# mppt.net
KiCad netlist of a schematic drawn in EAGLE
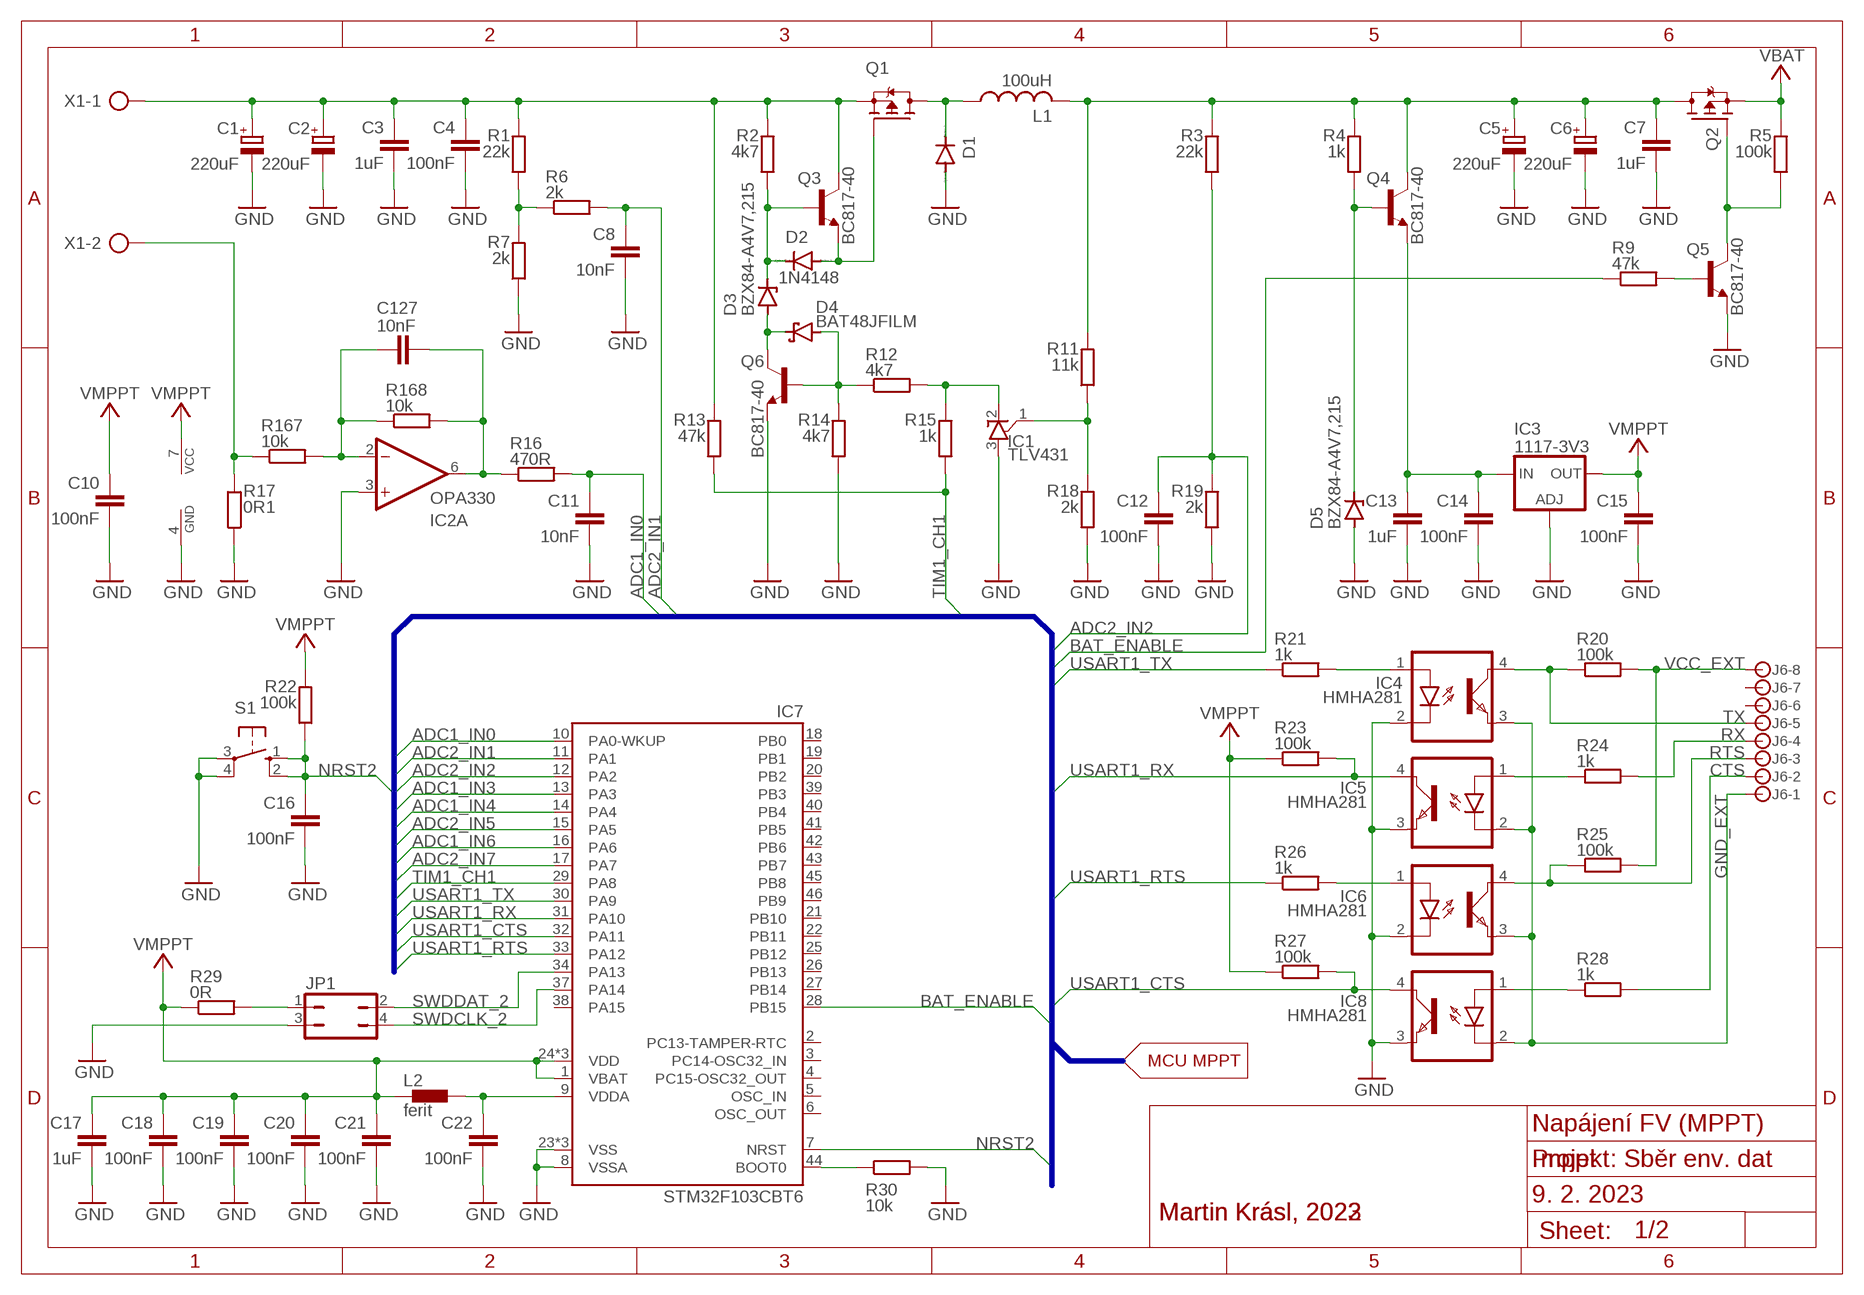
[diagram p0: schematic, sheet 1]
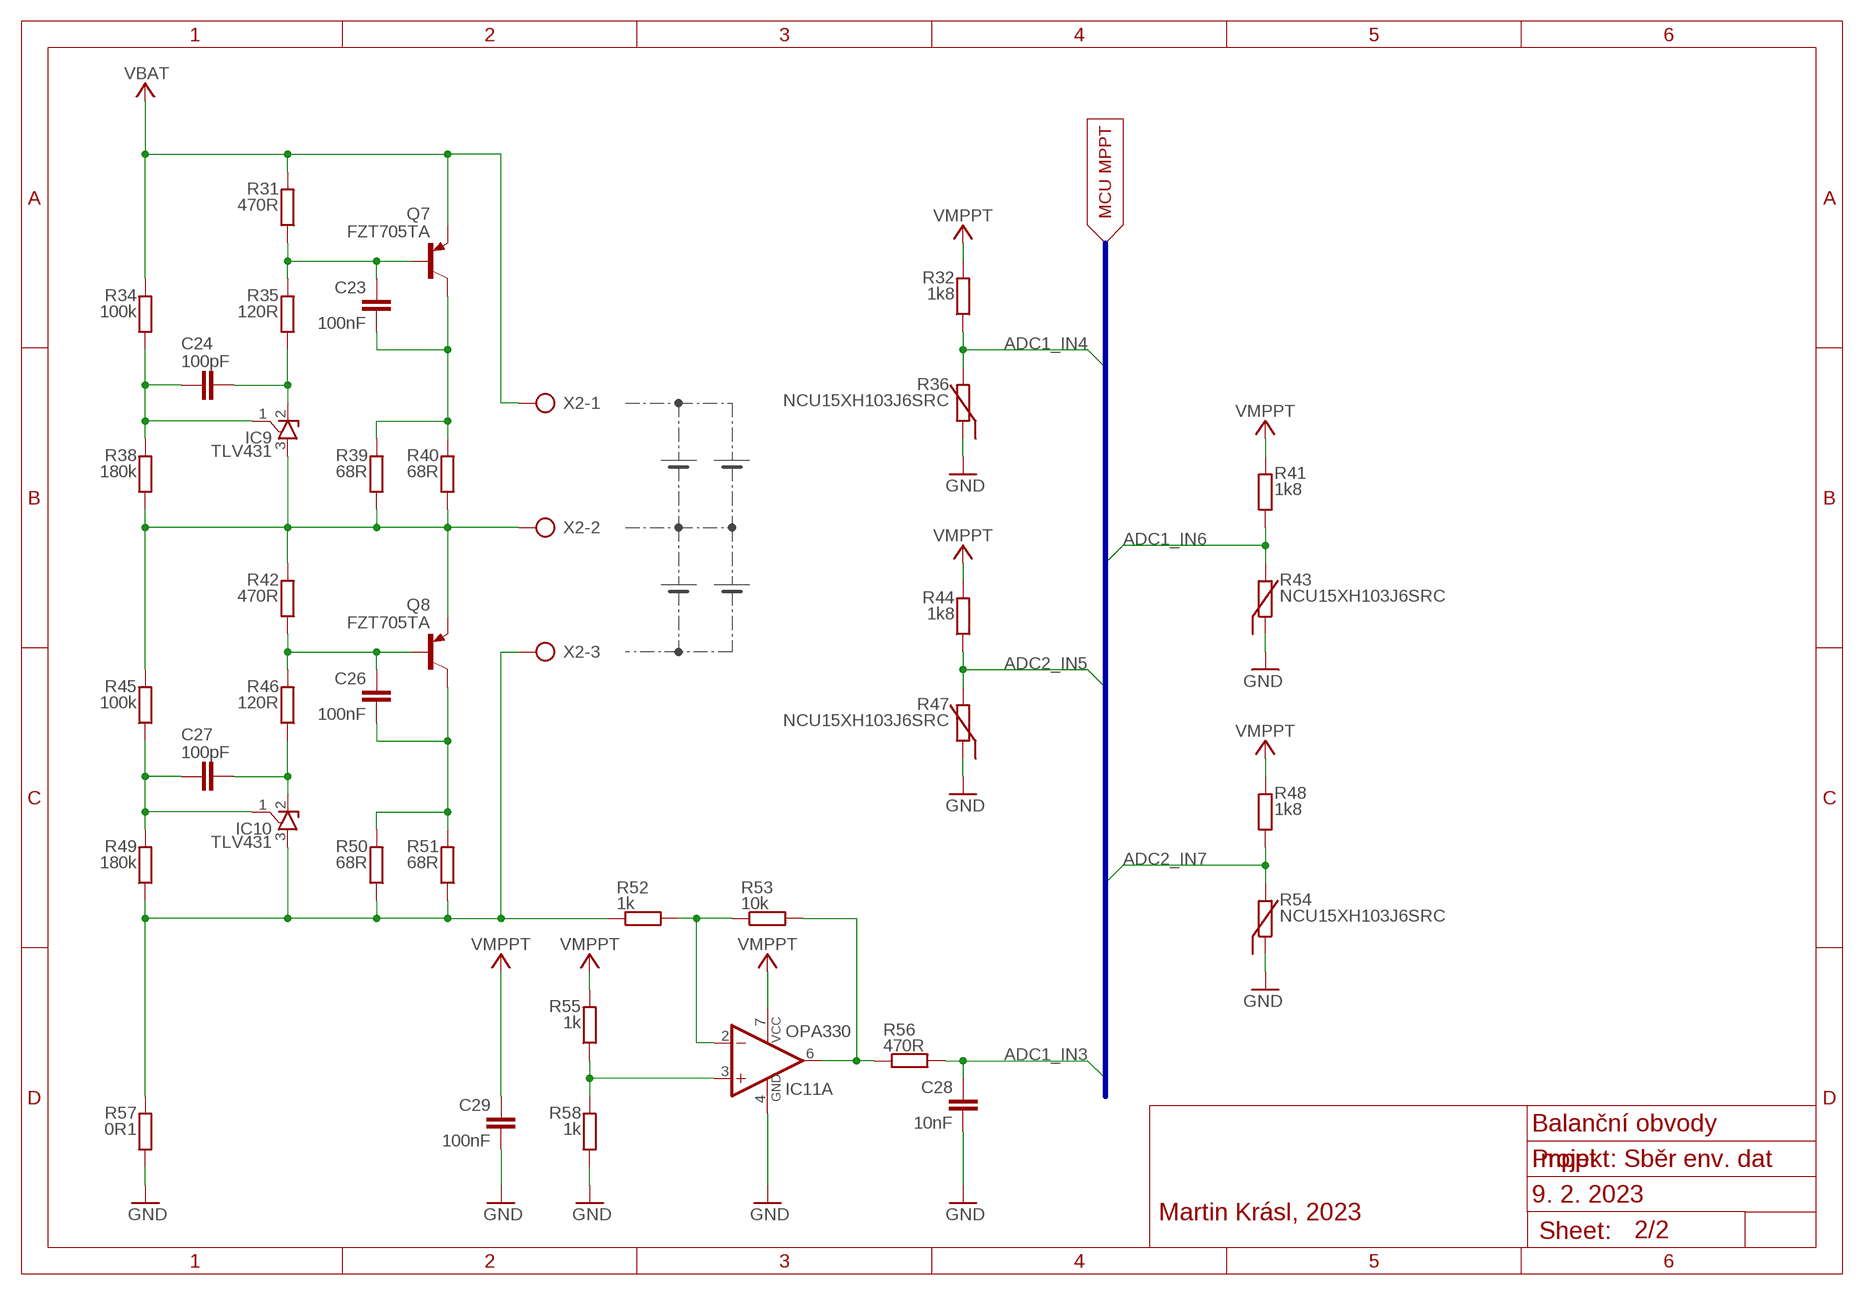
[diagram p1: schematic, sheet 2]

(export (version "E")
  (design (tool "Eeschema 10.0.6"))
  (components
    (comp (ref "C1")
      (value "220uF")
      (footprint "eagle-import:PANASONIC_G")
      (libsource (lib "eagle-import") (part "CPOL-EUG"))
    )
    (comp (ref "C2")
      (value "220uF")
      (footprint "eagle-import:PANASONIC_G")
      (libsource (lib "eagle-import") (part "CPOL-EUG"))
    )
    (comp (ref "C3")
      (value "1uF")
      (footprint "eagle-import:C0805")
      (libsource (lib "eagle-import") (part "C-EUC0805"))
    )
    (comp (ref "C4")
      (value "100nF")
      (footprint "eagle-import:C0402")
      (libsource (lib "eagle-import") (part "C-EUC0402"))
    )
    (comp (ref "C5")
      (value "220uF")
      (footprint "eagle-import:PANASONIC_G")
      (libsource (lib "eagle-import") (part "CPOL-EUG"))
    )
    (comp (ref "C6")
      (value "220uF")
      (footprint "eagle-import:PANASONIC_G")
      (libsource (lib "eagle-import") (part "CPOL-EUG"))
    )
    (comp (ref "C7")
      (value "1uF")
      (footprint "eagle-import:C0805")
      (libsource (lib "eagle-import") (part "C-EUC0805"))
    )
    (comp (ref "C8")
      (value "10nF")
      (footprint "eagle-import:C0402")
      (libsource (lib "eagle-import") (part "C-EUC0402"))
    )
    (comp (ref "C10")
      (value "100nF")
      (footprint "eagle-import:C0402")
      (libsource (lib "eagle-import") (part "C-EUC0402"))
    )
    (comp (ref "C11")
      (value "10nF")
      (footprint "eagle-import:C0402")
      (libsource (lib "eagle-import") (part "C-EUC0402"))
    )
    (comp (ref "C12")
      (value "100nF")
      (footprint "eagle-import:C0402")
      (libsource (lib "eagle-import") (part "C-EUC0402"))
    )
    (comp (ref "C13")
      (value "1uF")
      (footprint "eagle-import:C0805")
      (libsource (lib "eagle-import") (part "C-EUC0805"))
    )
    (comp (ref "C14")
      (value "100nF")
      (footprint "eagle-import:C0402")
      (libsource (lib "eagle-import") (part "C-EUC0402"))
    )
    (comp (ref "C15")
      (value "100nF")
      (footprint "eagle-import:C0402")
      (libsource (lib "eagle-import") (part "C-EUC0402"))
    )
    (comp (ref "C16")
      (value "100nF")
      (footprint "eagle-import:C0402")
      (libsource (lib "eagle-import") (part "C-EUC0402"))
    )
    (comp (ref "C17")
      (value "1uF")
      (footprint "eagle-import:C0805")
      (libsource (lib "eagle-import") (part "C-EUC0805"))
    )
    (comp (ref "C18")
      (value "100nF")
      (footprint "eagle-import:C0402")
      (libsource (lib "eagle-import") (part "C-EUC0402"))
    )
    (comp (ref "C19")
      (value "100nF")
      (footprint "eagle-import:C0402")
      (libsource (lib "eagle-import") (part "C-EUC0402"))
    )
    (comp (ref "C20")
      (value "100nF")
      (footprint "eagle-import:C0402")
      (libsource (lib "eagle-import") (part "C-EUC0402"))
    )
    (comp (ref "C21")
      (value "100nF")
      (footprint "eagle-import:C0402")
      (libsource (lib "eagle-import") (part "C-EUC0402"))
    )
    (comp (ref "C22")
      (value "100nF")
      (footprint "eagle-import:C0402")
      (libsource (lib "eagle-import") (part "C-EUC0402"))
    )
    (comp (ref "C127")
      (value "10nF")
      (footprint "eagle-import:C0402")
      (libsource (lib "eagle-import") (part "C-EUC0402"))
    )
    (comp (ref "D1")
      (value "#?")
      (footprint "eagle-import:SOD323")
      (libsource (lib "eagle-import") (part "1N4148"))
    )
    (comp (ref "D2")
      (value "1N4148")
      (footprint "eagle-import:SOD323")
      (libsource (lib "eagle-import") (part "1N4148"))
    )
    (comp (ref "D3")
      (value "BZX84-A4V7,215")
      (footprint "eagle-import:SOT23")
      (libsource (lib "eagle-import") (part "ZENER-DIODESOT23"))
    )
    (comp (ref "D4")
      (value "BAT48JFILM")
      (footprint "eagle-import:SOD323")
      (libsource (lib "eagle-import") (part "BAT48"))
    )
    (comp (ref "D5")
      (value "BZX84-A4V7,215")
      (footprint "eagle-import:SOT23")
      (libsource (lib "eagle-import") (part "ZENER-DIODESOT23"))
    )
    (comp (ref "IC1")
      (value "TLV431")
      (footprint "eagle-import:SOT23")
      (libsource (lib "eagle-import") (part "TLV431"))
    )
    (comp (ref "IC2")
      (value "OPA330")
      (footprint "eagle-import:SOIC-8")
      (libsource (lib "eagle-import") (part "OPA3"))
    )
    (comp (ref "IC3")
      (value "1117-3V3")
      (footprint "eagle-import:D2PACK")
      (libsource (lib "eagle-import") (part "LD117A?D2MTR"))
    )
    (comp (ref "IC4")
      (value "HMHA281")
      (footprint "eagle-import:SOIC127P680X239-4N")
      (fields (field (name "MOUSER_PART_NUMBER") "512-HMHA281"))
      (libsource (lib "eagle-import") (part "HMHA281"))
    )
    (comp (ref "IC5")
      (value "HMHA281")
      (footprint "eagle-import:SOIC127P680X239-4N")
      (fields (field (name "MOUSER_PART_NUMBER") "512-HMHA281"))
      (libsource (lib "eagle-import") (part "HMHA281"))
    )
    (comp (ref "IC6")
      (value "HMHA281")
      (footprint "eagle-import:SOIC127P680X239-4N")
      (fields (field (name "MOUSER_PART_NUMBER") "512-HMHA281"))
      (libsource (lib "eagle-import") (part "HMHA281"))
    )
    (comp (ref "IC7")
      (value "STM32F103CBT6")
      (footprint "eagle-import:QFP50P900X900X160-48N")
      (fields (field (name "MOUSER_PART_NUMBER") "511-STM32F103CBT6"))
      (libsource (lib "eagle-import") (part "STM32F103CBT6"))
    )
    (comp (ref "IC8")
      (value "HMHA281")
      (footprint "eagle-import:SOIC127P680X239-4N")
      (fields (field (name "MOUSER_PART_NUMBER") "512-HMHA281"))
      (libsource (lib "eagle-import") (part "HMHA281"))
    )
    (comp (ref "J6")
      (value "JST-XH-8")
      (footprint "eagle-import:B8B-XH-A")
      (fields (field (name "MF") "JST") (field (name "MPN") "B8B-XH-A"))
      (libsource (lib "eagle-import") (part "JST-XH-8"))
    )
    (comp (ref "JP1")
      (value "JP2Q")
      (footprint "eagle-import:JP2Q")
      (libsource (lib "eagle-import") (part "JP2Q"))
    )
    (comp (ref "L1")
      (value "100uH")
      (footprint "eagle-import:CEP125")
      (libsource (lib "eagle-import") (part "L-USCEP125"))
    )
    (comp (ref "L2")
      (value "ferit")
      (footprint "eagle-import:0402")
      (libsource (lib "eagle-import") (part "BLM15HB121SN1"))
    )
    (comp (ref "Q1")
      (value "#?")
      (footprint "eagle-import:SC74_INFINEON")
      (libsource (lib "eagle-import") (part "BSL207SP"))
    )
    (comp (ref "Q2")
      (value "#?")
      (footprint "eagle-import:SC74_INFINEON")
      (libsource (lib "eagle-import") (part "BSL207SP"))
    )
    (comp (ref "Q3")
      (value "BC817-40")
      (footprint "eagle-import:SOT23-BEC")
      (libsource (lib "eagle-import") (part "BC817SMD-16LT1"))
    )
    (comp (ref "Q4")
      (value "BC817-40")
      (footprint "eagle-import:SOT23-BEC")
      (libsource (lib "eagle-import") (part "BC817SMD-16LT1"))
    )
    (comp (ref "Q5")
      (value "BC817-40")
      (footprint "eagle-import:SOT23-BEC")
      (libsource (lib "eagle-import") (part "BC817SMD-16LT1"))
    )
    (comp (ref "Q6")
      (value "BC817-40")
      (footprint "eagle-import:SOT23-BEC")
      (libsource (lib "eagle-import") (part "BC817SMD-16LT1"))
    )
    (comp (ref "R1")
      (value "22k")
      (footprint "eagle-import:R0402")
      (libsource (lib "eagle-import") (part "R-EU_R0402"))
    )
    (comp (ref "R2")
      (value "4k7")
      (footprint "eagle-import:R0402")
      (libsource (lib "eagle-import") (part "R-EU_R0402"))
    )
    (comp (ref "R3")
      (value "22k")
      (footprint "eagle-import:R0402")
      (libsource (lib "eagle-import") (part "R-EU_R0402"))
    )
    (comp (ref "R4")
      (value "1k")
      (footprint "eagle-import:R0402")
      (libsource (lib "eagle-import") (part "R-EU_R0402"))
    )
    (comp (ref "R5")
      (value "100k")
      (footprint "eagle-import:R0402")
      (libsource (lib "eagle-import") (part "R-EU_R0402"))
    )
    (comp (ref "R6")
      (value "2k")
      (footprint "eagle-import:R0402")
      (libsource (lib "eagle-import") (part "R-EU_R0402"))
    )
    (comp (ref "R7")
      (value "2k")
      (footprint "eagle-import:R0402")
      (libsource (lib "eagle-import") (part "R-EU_R0402"))
    )
    (comp (ref "R9")
      (value "47k")
      (footprint "eagle-import:R0402")
      (libsource (lib "eagle-import") (part "R-EU_R0402"))
    )
    (comp (ref "R11")
      (value "11k")
      (footprint "eagle-import:R0402")
      (libsource (lib "eagle-import") (part "R-EU_R0402"))
    )
    (comp (ref "R12")
      (value "4k7")
      (footprint "eagle-import:R0402")
      (libsource (lib "eagle-import") (part "R-EU_R0402"))
    )
    (comp (ref "R13")
      (value "47k")
      (footprint "eagle-import:R0402")
      (libsource (lib "eagle-import") (part "R-EU_R0402"))
    )
    (comp (ref "R14")
      (value "4k7")
      (footprint "eagle-import:R0402")
      (libsource (lib "eagle-import") (part "R-EU_R0402"))
    )
    (comp (ref "R15")
      (value "1k")
      (footprint "eagle-import:R0402")
      (libsource (lib "eagle-import") (part "R-EU_R0402"))
    )
    (comp (ref "R16")
      (value "470R")
      (footprint "eagle-import:R0402")
      (libsource (lib "eagle-import") (part "R-EU_R0402"))
    )
    (comp (ref "R17")
      (value "0R1")
      (footprint "eagle-import:R0805")
      (libsource (lib "eagle-import") (part "R-EU_R0805"))
    )
    (comp (ref "R18")
      (value "2k")
      (footprint "eagle-import:R0402")
      (libsource (lib "eagle-import") (part "R-EU_R0402"))
    )
    (comp (ref "R19")
      (value "2k")
      (footprint "eagle-import:R0402")
      (libsource (lib "eagle-import") (part "R-EU_R0402"))
    )
    (comp (ref "R20")
      (value "100k")
      (footprint "eagle-import:R0402")
      (libsource (lib "eagle-import") (part "R-EU_R0402"))
    )
    (comp (ref "R21")
      (value "1k")
      (footprint "eagle-import:R0402")
      (libsource (lib "eagle-import") (part "R-EU_R0402"))
    )
    (comp (ref "R22")
      (value "100k")
      (footprint "eagle-import:R0402")
      (libsource (lib "eagle-import") (part "R-EU_R0402"))
    )
    (comp (ref "R23")
      (value "100k")
      (footprint "eagle-import:R0402")
      (libsource (lib "eagle-import") (part "R-EU_R0402"))
    )
    (comp (ref "R24")
      (value "1k")
      (footprint "eagle-import:R0402")
      (libsource (lib "eagle-import") (part "R-EU_R0402"))
    )
    (comp (ref "R25")
      (value "100k")
      (footprint "eagle-import:R0402")
      (libsource (lib "eagle-import") (part "R-EU_R0402"))
    )
    (comp (ref "R26")
      (value "1k")
      (footprint "eagle-import:R0402")
      (libsource (lib "eagle-import") (part "R-EU_R0402"))
    )
    (comp (ref "R27")
      (value "100k")
      (footprint "eagle-import:R0402")
      (libsource (lib "eagle-import") (part "R-EU_R0402"))
    )
    (comp (ref "R28")
      (value "1k")
      (footprint "eagle-import:R0402")
      (libsource (lib "eagle-import") (part "R-EU_R0402"))
    )
    (comp (ref "R29")
      (value "0R")
      (footprint "eagle-import:R0402")
      (libsource (lib "eagle-import") (part "R-EU_R0402"))
    )
    (comp (ref "R30")
      (value "10k")
      (footprint "eagle-import:R0402")
      (libsource (lib "eagle-import") (part "R-EU_R0402"))
    )
    (comp (ref "R167")
      (value "10k")
      (footprint "eagle-import:R0402")
      (libsource (lib "eagle-import") (part "R-EU_R0402"))
    )
    (comp (ref "R168")
      (value "10k")
      (footprint "eagle-import:R0402")
      (libsource (lib "eagle-import") (part "R-EU_R0402"))
    )
    (comp (ref "S1")
      (value "10-XX")
      (footprint "eagle-import:B3F-10XX")
      (fields (field (name "MPN") "B3F-1000"))
      (libsource (lib "eagle-import") (part "10-XX"))
    )
    (comp (ref "X1")
      (value "AK500/2")
      (footprint "eagle-import:AK500_2")
      (libsource (lib "eagle-import") (part "AK500/2"))
    )
    (comp (ref "C23")
      (value "100nF")
      (footprint "eagle-import:C0402")
      (libsource (lib "eagle-import") (part "C-EUC0402"))
    )
    (comp (ref "C24")
      (value "100pF")
      (footprint "eagle-import:C0402")
      (libsource (lib "eagle-import") (part "C-EUC0402"))
    )
    (comp (ref "C26")
      (value "100nF")
      (footprint "eagle-import:C0402")
      (libsource (lib "eagle-import") (part "C-EUC0402"))
    )
    (comp (ref "C27")
      (value "100pF")
      (footprint "eagle-import:C0402")
      (libsource (lib "eagle-import") (part "C-EUC0402"))
    )
    (comp (ref "C28")
      (value "10nF")
      (footprint "eagle-import:C0402")
      (libsource (lib "eagle-import") (part "C-EUC0402"))
    )
    (comp (ref "C29")
      (value "100nF")
      (footprint "eagle-import:C0402")
      (libsource (lib "eagle-import") (part "C-EUC0402"))
    )
    (comp (ref "IC9")
      (value "TLV431")
      (footprint "eagle-import:SOT23")
      (libsource (lib "eagle-import") (part "TLV431"))
    )
    (comp (ref "IC10")
      (value "TLV431")
      (footprint "eagle-import:SOT23")
      (libsource (lib "eagle-import") (part "TLV431"))
    )
    (comp (ref "IC11")
      (value "OPA330")
      (footprint "eagle-import:SOIC-8")
      (libsource (lib "eagle-import") (part "OPA3"))
    )
    (comp (ref "Q7")
      (value "FZT705TA")
      (footprint "eagle-import:SOT223")
      (libsource (lib "eagle-import") (part "FZT753SMD"))
    )
    (comp (ref "Q8")
      (value "FZT705TA")
      (footprint "eagle-import:SOT223")
      (libsource (lib "eagle-import") (part "FZT753SMD"))
    )
    (comp (ref "R31")
      (value "470R")
      (footprint "eagle-import:R0402")
      (libsource (lib "eagle-import") (part "R-EU_R0402"))
    )
    (comp (ref "R32")
      (value "1k8")
      (footprint "eagle-import:R0402")
      (libsource (lib "eagle-import") (part "R-EU_R0402"))
    )
    (comp (ref "R34")
      (value "100k")
      (footprint "eagle-import:R0402")
      (libsource (lib "eagle-import") (part "R-EU_R0402"))
    )
    (comp (ref "R35")
      (value "120R")
      (footprint "eagle-import:R0402")
      (libsource (lib "eagle-import") (part "R-EU_R0402"))
    )
    (comp (ref "R36")
      (value "NCU15XH103J6SRC")
      (footprint "eagle-import:R0402")
      (libsource (lib "eagle-import") (part "NCU15XH103J6SRC"))
    )
    (comp (ref "R38")
      (value "180k")
      (footprint "eagle-import:R0402")
      (libsource (lib "eagle-import") (part "R-EU_R0402"))
    )
    (comp (ref "R39")
      (value "68R")
      (footprint "eagle-import:R2512")
      (libsource (lib "eagle-import") (part "R-EU_R2512"))
    )
    (comp (ref "R40")
      (value "68R")
      (footprint "eagle-import:R2512")
      (libsource (lib "eagle-import") (part "R-EU_R2512"))
    )
    (comp (ref "R41")
      (value "1k8")
      (footprint "eagle-import:R0402")
      (libsource (lib "eagle-import") (part "R-EU_R0402"))
    )
    (comp (ref "R42")
      (value "470R")
      (footprint "eagle-import:R0402")
      (libsource (lib "eagle-import") (part "R-EU_R0402"))
    )
    (comp (ref "R43")
      (value "NCU15XH103J6SRC")
      (footprint "eagle-import:R0402")
      (libsource (lib "eagle-import") (part "NCU15XH103J6SRC"))
    )
    (comp (ref "R44")
      (value "1k8")
      (footprint "eagle-import:R0402")
      (libsource (lib "eagle-import") (part "R-EU_R0402"))
    )
    (comp (ref "R45")
      (value "100k")
      (footprint "eagle-import:R0402")
      (libsource (lib "eagle-import") (part "R-EU_R0402"))
    )
    (comp (ref "R46")
      (value "120R")
      (footprint "eagle-import:R0402")
      (libsource (lib "eagle-import") (part "R-EU_R0402"))
    )
    (comp (ref "R47")
      (value "NCU15XH103J6SRC")
      (footprint "eagle-import:R0402")
      (libsource (lib "eagle-import") (part "NCU15XH103J6SRC"))
    )
    (comp (ref "R48")
      (value "1k8")
      (footprint "eagle-import:R0402")
      (libsource (lib "eagle-import") (part "R-EU_R0402"))
    )
    (comp (ref "R49")
      (value "180k")
      (footprint "eagle-import:R0402")
      (libsource (lib "eagle-import") (part "R-EU_R0402"))
    )
    (comp (ref "R50")
      (value "68R")
      (footprint "eagle-import:R2512")
      (libsource (lib "eagle-import") (part "R-EU_R2512"))
    )
    (comp (ref "R51")
      (value "68R")
      (footprint "eagle-import:R2512")
      (libsource (lib "eagle-import") (part "R-EU_R2512"))
    )
    (comp (ref "R52")
      (value "1k")
      (footprint "eagle-import:R0402")
      (libsource (lib "eagle-import") (part "R-EU_R0402"))
    )
    (comp (ref "R53")
      (value "10k")
      (footprint "eagle-import:R0402")
      (libsource (lib "eagle-import") (part "R-EU_R0402"))
    )
    (comp (ref "R54")
      (value "NCU15XH103J6SRC")
      (footprint "eagle-import:R0402")
      (libsource (lib "eagle-import") (part "NCU15XH103J6SRC"))
    )
    (comp (ref "R55")
      (value "1k")
      (footprint "eagle-import:R0402")
      (libsource (lib "eagle-import") (part "R-EU_R0402"))
    )
    (comp (ref "R56")
      (value "470R")
      (footprint "eagle-import:R0402")
      (libsource (lib "eagle-import") (part "R-EU_R0402"))
    )
    (comp (ref "R57")
      (value "0R1")
      (footprint "eagle-import:R0805")
      (libsource (lib "eagle-import") (part "R-EU_R0805"))
    )
    (comp (ref "R58")
      (value "1k")
      (footprint "eagle-import:R0402")
      (libsource (lib "eagle-import") (part "R-EU_R0402"))
    )
    (comp (ref "X2")
      (value "AK500/3")
      (footprint "eagle-import:AK500_3")
      (libsource (lib "eagle-import") (part "AK500/3"))
    )
  )
  (nets
    (net (code "1") (name "ADC1_IN0") (class "Default")
      (node (ref "C11") (pin "1") (pinfunction "1_1") (pintype "passive"))
      (node (ref "IC7") (pin "10") (pinfunction "PA0-WKUP_10") (pintype "bidirectional"))
      (node (ref "R16") (pin "2") (pinfunction "2_2") (pintype "passive"))
    )
    (net (code "2") (name "ADC1_IN3") (class "Default")
      (node (ref "C28") (pin "1") (pinfunction "1_1") (pintype "passive"))
      (node (ref "IC7") (pin "13") (pinfunction "PA3_13") (pintype "bidirectional"))
      (node (ref "R56") (pin "2") (pinfunction "2_2") (pintype "passive"))
    )
    (net (code "3") (name "ADC1_IN4") (class "Default")
      (node (ref "IC7") (pin "14") (pinfunction "PA4_14") (pintype "bidirectional"))
      (node (ref "R32") (pin "1") (pinfunction "1_1") (pintype "passive"))
      (node (ref "R36") (pin "2") (pinfunction "2_2") (pintype "passive"))
    )
    (net (code "4") (name "ADC1_IN6") (class "Default")
      (node (ref "IC7") (pin "16") (pinfunction "PA6_16") (pintype "bidirectional"))
      (node (ref "R41") (pin "1") (pinfunction "1_1") (pintype "passive"))
      (node (ref "R43") (pin "2") (pinfunction "2_2") (pintype "passive"))
    )
    (net (code "5") (name "ADC2_IN1") (class "Default")
      (node (ref "C8") (pin "1") (pinfunction "1_1") (pintype "passive"))
      (node (ref "IC7") (pin "11") (pinfunction "PA1_11") (pintype "bidirectional"))
      (node (ref "R6") (pin "2") (pinfunction "2_2") (pintype "passive"))
    )
    (net (code "6") (name "ADC2_IN2") (class "Default")
      (node (ref "C12") (pin "1") (pinfunction "1_1") (pintype "passive"))
      (node (ref "IC7") (pin "12") (pinfunction "PA2_12") (pintype "bidirectional"))
      (node (ref "R19") (pin "2") (pinfunction "2_2") (pintype "passive"))
      (node (ref "R3") (pin "1") (pinfunction "1_1") (pintype "passive"))
    )
    (net (code "7") (name "ADC2_IN5") (class "Default")
      (node (ref "IC7") (pin "15") (pinfunction "PA5_15") (pintype "bidirectional"))
      (node (ref "R44") (pin "1") (pinfunction "1_1") (pintype "passive"))
      (node (ref "R47") (pin "2") (pinfunction "2_2") (pintype "passive"))
    )
    (net (code "8") (name "ADC2_IN7") (class "Default")
      (node (ref "IC7") (pin "17") (pinfunction "PA7_17") (pintype "bidirectional"))
      (node (ref "R48") (pin "1") (pinfunction "1_1") (pintype "passive"))
      (node (ref "R54") (pin "2") (pinfunction "2_2") (pintype "passive"))
    )
    (net (code "9") (name "BAT_ENABLE") (class "Default")
      (node (ref "IC7") (pin "28") (pinfunction "PB15_28") (pintype "bidirectional"))
      (node (ref "R9") (pin "1") (pinfunction "1_1") (pintype "passive"))
    )
    (net (code "10") (name "CTS") (class "Default")
      (node (ref "J6") (pin "2") (pinfunction "P_2") (pintype "bidirectional"))
      (node (ref "R28") (pin "2") (pinfunction "2_2") (pintype "passive"))
    )
    (net (code "11") (name "GND") (class "Default")
      (node (ref "C1") (pin "-") (pinfunction "-_-") (pintype "passive"))
      (node (ref "C10") (pin "2") (pinfunction "2_2") (pintype "passive"))
      (node (ref "C11") (pin "2") (pinfunction "2_2") (pintype "passive"))
      (node (ref "C12") (pin "2") (pinfunction "2_2") (pintype "passive"))
      (node (ref "C13") (pin "2") (pinfunction "2_2") (pintype "passive"))
      (node (ref "C14") (pin "2") (pinfunction "2_2") (pintype "passive"))
      (node (ref "C15") (pin "2") (pinfunction "2_2") (pintype "passive"))
      (node (ref "C16") (pin "2") (pinfunction "2_2") (pintype "passive"))
      (node (ref "C17") (pin "2") (pinfunction "2_2") (pintype "passive"))
      (node (ref "C18") (pin "2") (pinfunction "2_2") (pintype "passive"))
      (node (ref "C19") (pin "2") (pinfunction "2_2") (pintype "passive"))
      (node (ref "C2") (pin "-") (pinfunction "-_-") (pintype "passive"))
      (node (ref "C20") (pin "2") (pinfunction "2_2") (pintype "passive"))
      (node (ref "C21") (pin "2") (pinfunction "2_2") (pintype "passive"))
      (node (ref "C22") (pin "2") (pinfunction "2_2") (pintype "passive"))
      (node (ref "C28") (pin "2") (pinfunction "2_2") (pintype "passive"))
      (node (ref "C29") (pin "2") (pinfunction "2_2") (pintype "passive"))
      (node (ref "C3") (pin "2") (pinfunction "2_2") (pintype "passive"))
      (node (ref "C4") (pin "2") (pinfunction "2_2") (pintype "passive"))
      (node (ref "C5") (pin "-") (pinfunction "-_-") (pintype "passive"))
      (node (ref "C6") (pin "-") (pinfunction "-_-") (pintype "passive"))
      (node (ref "C7") (pin "2") (pinfunction "2_2") (pintype "passive"))
      (node (ref "C8") (pin "2") (pinfunction "2_2") (pintype "passive"))
      (node (ref "D1") (pin "2") (pinfunction "A_2") (pintype "passive"))
      (node (ref "D5") (pin "1") (pinfunction "A_1") (pintype "passive"))
      (node (ref "IC1") (pin "3") (pinfunction "A_3") (pintype "passive"))
      (node (ref "IC11") (pin "4") (pinfunction "GND_4") (pintype "power_in"))
      (node (ref "IC2") (pin "3") (pinfunction "+IN_3") (pintype "input"))
      (node (ref "IC2") (pin "4") (pinfunction "GND_4") (pintype "power_in"))
      (node (ref "IC3") (pin "1") (pinfunction "ADJ_1") (pintype "input"))
      (node (ref "IC4") (pin "2") (pinfunction "K_2") (pintype "bidirectional"))
      (node (ref "IC5") (pin "3") (pinfunction "E_3") (pintype "bidirectional"))
      (node (ref "IC6") (pin "2") (pinfunction "K_2") (pintype "bidirectional"))
      (node (ref "IC7") (pin "23") (pinfunction "VSS_23") (pintype "bidirectional"))
      (node (ref "IC7") (pin "35") (pinfunction "VSS_35") (pintype "bidirectional"))
      (node (ref "IC7") (pin "47") (pinfunction "VSS_47") (pintype "bidirectional"))
      (node (ref "IC7") (pin "8") (pinfunction "VSSA_8") (pintype "bidirectional"))
      (node (ref "IC8") (pin "3") (pinfunction "E_3") (pintype "bidirectional"))
      (node (ref "JP1") (pin "3") (pinfunction "3_3") (pintype "passive"))
      (node (ref "Q5") (pin "E") (pinfunction "E_E") (pintype "passive"))
      (node (ref "Q6") (pin "E") (pinfunction "E_E") (pintype "passive"))
      (node (ref "R14") (pin "1") (pinfunction "1_1") (pintype "passive"))
      (node (ref "R17") (pin "1") (pinfunction "1_1") (pintype "passive"))
      (node (ref "R18") (pin "1") (pinfunction "1_1") (pintype "passive"))
      (node (ref "R19") (pin "1") (pinfunction "1_1") (pintype "passive"))
      (node (ref "R30") (pin "2") (pinfunction "2_2") (pintype "passive"))
      (node (ref "R36") (pin "1") (pinfunction "1_1") (pintype "passive"))
      (node (ref "R43") (pin "1") (pinfunction "1_1") (pintype "passive"))
      (node (ref "R47") (pin "1") (pinfunction "1_1") (pintype "passive"))
      (node (ref "R54") (pin "1") (pinfunction "1_1") (pintype "passive"))
      (node (ref "R57") (pin "1") (pinfunction "1_1") (pintype "passive"))
      (node (ref "R58") (pin "1") (pinfunction "1_1") (pintype "passive"))
      (node (ref "R7") (pin "1") (pinfunction "1_1") (pintype "passive"))
      (node (ref "S1") (pin "3") (pinfunction "P_3") (pintype "passive"))
      (node (ref "S1") (pin "4") (pinfunction "P1_4") (pintype "passive"))
    )
    (net (code "12") (name "GND_EXT") (class "Default")
      (node (ref "IC4") (pin "3") (pinfunction "E_3") (pintype "bidirectional"))
      (node (ref "IC5") (pin "2") (pinfunction "K_2") (pintype "bidirectional"))
      (node (ref "IC6") (pin "3") (pinfunction "E_3") (pintype "bidirectional"))
      (node (ref "IC8") (pin "2") (pinfunction "K_2") (pintype "bidirectional"))
      (node (ref "J6") (pin "1") (pinfunction "P_1") (pintype "bidirectional"))
    )
    (net (code "13") (name "NRST2") (class "Default")
      (node (ref "C16") (pin "1") (pinfunction "1_1") (pintype "passive"))
      (node (ref "IC7") (pin "7") (pinfunction "NRST_7") (pintype "bidirectional"))
      (node (ref "R22") (pin "1") (pinfunction "1_1") (pintype "passive"))
      (node (ref "S1") (pin "1") (pinfunction "S_1") (pintype "passive"))
      (node (ref "S1") (pin "2") (pinfunction "S1_2") (pintype "passive"))
    )
    (net (code "14") (name "Net-(C5-Pad+)") (class "Default")
      (node (ref "C5") (pin "+") (pinfunction "+_+") (pintype "passive"))
      (node (ref "C6") (pin "+") (pinfunction "+_+") (pintype "passive"))
      (node (ref "C7") (pin "1") (pinfunction "1_1") (pintype "passive"))
      (node (ref "L1") (pin "2") (pinfunction "2_2") (pintype "passive"))
      (node (ref "Q2") (pin "1") (pinfunction "D_1") (pintype "passive"))
      (node (ref "Q2") (pin "2") (pinfunction "D_2") (pintype "passive"))
      (node (ref "Q2") (pin "5") (pinfunction "D_5") (pintype "passive"))
      (node (ref "Q2") (pin "6") (pinfunction "D_6") (pintype "passive"))
      (node (ref "Q4") (pin "C") (pinfunction "C_C") (pintype "passive"))
      (node (ref "R11") (pin "2") (pinfunction "2_2") (pintype "passive"))
      (node (ref "R3") (pin "2") (pinfunction "2_2") (pintype "passive"))
      (node (ref "R4") (pin "2") (pinfunction "2_2") (pintype "passive"))
    )
    (net (code "15") (name "Net-(C23-Pad2)") (class "Default")
      (node (ref "C23") (pin "2") (pinfunction "2_2") (pintype "passive"))
      (node (ref "Q7") (pin "2") (pinfunction "C_2") (pintype "passive"))
      (node (ref "Q7") (pin "4") (pinfunction "C_4") (pintype "passive"))
      (node (ref "R39") (pin "2") (pinfunction "2_2") (pintype "passive"))
      (node (ref "R40") (pin "2") (pinfunction "2_2") (pintype "passive"))
    )
    (net (code "16") (name "Net-(C26-Pad2)") (class "Default")
      (node (ref "C26") (pin "2") (pinfunction "2_2") (pintype "passive"))
      (node (ref "Q8") (pin "2") (pinfunction "C_2") (pintype "passive"))
      (node (ref "Q8") (pin "4") (pinfunction "C_4") (pintype "passive"))
      (node (ref "R50") (pin "2") (pinfunction "2_2") (pintype "passive"))
      (node (ref "R51") (pin "2") (pinfunction "2_2") (pintype "passive"))
    )
    (net (code "17") (name "Net-(D1-C)") (class "Default")
      (node (ref "D1") (pin "1") (pinfunction "C_1") (pintype "passive"))
      (node (ref "L1") (pin "1") (pinfunction "1_1") (pintype "passive"))
      (node (ref "Q1") (pin "1") (pinfunction "D_1") (pintype "passive"))
      (node (ref "Q1") (pin "2") (pinfunction "D_2") (pintype "passive"))
      (node (ref "Q1") (pin "5") (pinfunction "D_5") (pintype "passive"))
      (node (ref "Q1") (pin "6") (pinfunction "D_6") (pintype "passive"))
    )
    (net (code "18") (name "Net-(D2-A)") (class "Default")
      (node (ref "D2") (pin "2") (pinfunction "A_2") (pintype "passive"))
      (node (ref "Q1") (pin "3") (pinfunction "G_3") (pintype "passive"))
      (node (ref "Q3") (pin "E") (pinfunction "E_E") (pintype "passive"))
    )
    (net (code "19") (name "Net-(D2-C)") (class "Default")
      (node (ref "D2") (pin "1") (pinfunction "C_1") (pintype "passive"))
      (node (ref "D3") (pin "3") (pinfunction "C_3") (pintype "passive"))
      (node (ref "Q3") (pin "B") (pinfunction "B_B") (pintype "passive"))
      (node (ref "R2") (pin "1") (pinfunction "1_1") (pintype "passive"))
    )
    (net (code "20") (name "Net-(D3-A)") (class "Default")
      (node (ref "D3") (pin "1") (pinfunction "A_1") (pintype "passive"))
      (node (ref "D4") (pin "1") (pinfunction "C_1") (pintype "passive"))
      (node (ref "Q6") (pin "C") (pinfunction "C_C") (pintype "passive"))
    )
    (net (code "21") (name "Net-(D4-A)") (class "Default")
      (node (ref "D4") (pin "2") (pinfunction "A_2") (pintype "passive"))
      (node (ref "Q6") (pin "B") (pinfunction "B_B") (pintype "passive"))
      (node (ref "R12") (pin "1") (pinfunction "1_1") (pintype "passive"))
      (node (ref "R14") (pin "2") (pinfunction "2_2") (pintype "passive"))
    )
    (net (code "22") (name "Net-(D5-C)") (class "Default")
      (node (ref "D5") (pin "3") (pinfunction "C_3") (pintype "passive"))
      (node (ref "Q4") (pin "B") (pinfunction "B_B") (pintype "passive"))
      (node (ref "R4") (pin "1") (pinfunction "1_1") (pintype "passive"))
    )
    (net (code "23") (name "Net-(IC1-C)") (class "Default")
      (node (ref "IC1") (pin "2") (pinfunction "C_2") (pintype "passive"))
      (node (ref "R12") (pin "2") (pinfunction "2_2") (pintype "passive"))
      (node (ref "R15") (pin "2") (pinfunction "2_2") (pintype "passive"))
    )
    (net (code "24") (name "Net-(IC1-R)") (class "Default")
      (node (ref "IC1") (pin "1") (pinfunction "R_1") (pintype "passive"))
      (node (ref "R11") (pin "1") (pinfunction "1_1") (pintype "passive"))
      (node (ref "R18") (pin "2") (pinfunction "2_2") (pintype "passive"))
    )
    (net (code "25") (name "Net-(IC2A--IN)") (class "Default")
      (node (ref "C127") (pin "1") (pinfunction "1_1") (pintype "passive"))
      (node (ref "IC2") (pin "2") (pinfunction "-IN_2") (pintype "input"))
      (node (ref "R167") (pin "2") (pinfunction "2_2") (pintype "passive"))
      (node (ref "R168") (pin "1") (pinfunction "1_1") (pintype "passive"))
    )
    (net (code "26") (name "Net-(IC2A-OUT)") (class "Default")
      (node (ref "C127") (pin "2") (pinfunction "2_2") (pintype "passive"))
      (node (ref "IC2") (pin "6") (pinfunction "OUT_6") (pintype "output"))
      (node (ref "R16") (pin "1") (pinfunction "1_1") (pintype "passive"))
      (node (ref "R168") (pin "2") (pinfunction "2_2") (pintype "passive"))
    )
    (net (code "27") (name "Net-(IC3-IN)") (class "Default")
      (node (ref "C13") (pin "1") (pinfunction "1_1") (pintype "passive"))
      (node (ref "C14") (pin "1") (pinfunction "1_1") (pintype "passive"))
      (node (ref "IC3") (pin "3") (pinfunction "IN_3") (pintype "input"))
      (node (ref "Q4") (pin "E") (pinfunction "E_E") (pintype "passive"))
    )
    (net (code "28") (name "Net-(IC4-A)") (class "Default")
      (node (ref "IC4") (pin "1") (pinfunction "A_1") (pintype "bidirectional"))
      (node (ref "R21") (pin "2") (pinfunction "2_2") (pintype "passive"))
    )
    (net (code "29") (name "Net-(IC5-A)") (class "Default")
      (node (ref "IC5") (pin "1") (pinfunction "A_1") (pintype "bidirectional"))
      (node (ref "R24") (pin "1") (pinfunction "1_1") (pintype "passive"))
    )
    (net (code "30") (name "Net-(IC6-A)") (class "Default")
      (node (ref "IC6") (pin "1") (pinfunction "A_1") (pintype "bidirectional"))
      (node (ref "R26") (pin "2") (pinfunction "2_2") (pintype "passive"))
    )
    (net (code "31") (name "Net-(IC7-BOOT0)") (class "Default")
      (node (ref "IC7") (pin "44") (pinfunction "BOOT0_44") (pintype "bidirectional"))
      (node (ref "R30") (pin "1") (pinfunction "1_1") (pintype "passive"))
    )
    (net (code "32") (name "Net-(IC7-VDDA)") (class "Default")
      (node (ref "C22") (pin "1") (pinfunction "1_1") (pintype "passive"))
      (node (ref "IC7") (pin "9") (pinfunction "VDDA_9") (pintype "bidirectional"))
      (node (ref "L2") (pin "2") (pinfunction "2_2") (pintype "passive"))
    )
    (net (code "33") (name "Net-(IC8-A)") (class "Default")
      (node (ref "IC8") (pin "1") (pinfunction "A_1") (pintype "bidirectional"))
      (node (ref "R28") (pin "1") (pinfunction "1_1") (pintype "passive"))
    )
    (net (code "34") (name "Net-(IC9-A)") (class "Default")
      (node (ref "IC9") (pin "3") (pinfunction "A_3") (pintype "passive"))
      (node (ref "Q8") (pin "3") (pinfunction "E_3") (pintype "passive"))
      (node (ref "R38") (pin "1") (pinfunction "1_1") (pintype "passive"))
      (node (ref "R39") (pin "1") (pinfunction "1_1") (pintype "passive"))
      (node (ref "R40") (pin "1") (pinfunction "1_1") (pintype "passive"))
      (node (ref "R42") (pin "2") (pinfunction "2_2") (pintype "passive"))
      (node (ref "R45") (pin "2") (pinfunction "2_2") (pintype "passive"))
      (node (ref "X2") (pin "2") (pinfunction "KL_2") (pintype "passive"))
    )
    (net (code "35") (name "Net-(IC9-C)") (class "Default")
      (node (ref "C24") (pin "2") (pinfunction "2_2") (pintype "passive"))
      (node (ref "IC9") (pin "2") (pinfunction "C_2") (pintype "passive"))
      (node (ref "R35") (pin "1") (pinfunction "1_1") (pintype "passive"))
    )
    (net (code "36") (name "Net-(IC9-R)") (class "Default")
      (node (ref "C24") (pin "1") (pinfunction "1_1") (pintype "passive"))
      (node (ref "IC9") (pin "1") (pinfunction "R_1") (pintype "passive"))
      (node (ref "R34") (pin "1") (pinfunction "1_1") (pintype "passive"))
      (node (ref "R38") (pin "2") (pinfunction "2_2") (pintype "passive"))
    )
    (net (code "37") (name "Net-(IC10-A)") (class "Default")
      (node (ref "IC10") (pin "3") (pinfunction "A_3") (pintype "passive"))
      (node (ref "R49") (pin "1") (pinfunction "1_1") (pintype "passive"))
      (node (ref "R50") (pin "1") (pinfunction "1_1") (pintype "passive"))
      (node (ref "R51") (pin "1") (pinfunction "1_1") (pintype "passive"))
      (node (ref "R52") (pin "1") (pinfunction "1_1") (pintype "passive"))
      (node (ref "R57") (pin "2") (pinfunction "2_2") (pintype "passive"))
      (node (ref "X2") (pin "3") (pinfunction "KL_3") (pintype "passive"))
    )
    (net (code "38") (name "Net-(IC10-C)") (class "Default")
      (node (ref "C27") (pin "2") (pinfunction "2_2") (pintype "passive"))
      (node (ref "IC10") (pin "2") (pinfunction "C_2") (pintype "passive"))
      (node (ref "R46") (pin "1") (pinfunction "1_1") (pintype "passive"))
    )
    (net (code "39") (name "Net-(IC10-R)") (class "Default")
      (node (ref "C27") (pin "1") (pinfunction "1_1") (pintype "passive"))
      (node (ref "IC10") (pin "1") (pinfunction "R_1") (pintype "passive"))
      (node (ref "R45") (pin "1") (pinfunction "1_1") (pintype "passive"))
      (node (ref "R49") (pin "2") (pinfunction "2_2") (pintype "passive"))
    )
    (net (code "40") (name "Net-(IC11A-+IN)") (class "Default")
      (node (ref "IC11") (pin "3") (pinfunction "+IN_3") (pintype "input"))
      (node (ref "R55") (pin "1") (pinfunction "1_1") (pintype "passive"))
      (node (ref "R58") (pin "2") (pinfunction "2_2") (pintype "passive"))
    )
    (net (code "41") (name "Net-(IC11A--IN)") (class "Default")
      (node (ref "IC11") (pin "2") (pinfunction "-IN_2") (pintype "input"))
      (node (ref "R52") (pin "2") (pinfunction "2_2") (pintype "passive"))
      (node (ref "R53") (pin "1") (pinfunction "1_1") (pintype "passive"))
    )
    (net (code "42") (name "Net-(IC11A-OUT)") (class "Default")
      (node (ref "IC11") (pin "6") (pinfunction "OUT_6") (pintype "output"))
      (node (ref "R53") (pin "2") (pinfunction "2_2") (pintype "passive"))
      (node (ref "R56") (pin "1") (pinfunction "1_1") (pintype "passive"))
    )
    (net (code "43") (name "Net-(JP1-Pad1)") (class "Default")
      (node (ref "JP1") (pin "1") (pinfunction "1_1") (pintype "passive"))
      (node (ref "R29") (pin "2") (pinfunction "2_2") (pintype "passive"))
    )
    (net (code "44") (name "Net-(Q1-S)") (class "Default")
      (node (ref "C1") (pin "+") (pinfunction "+_+") (pintype "passive"))
      (node (ref "C2") (pin "+") (pinfunction "+_+") (pintype "passive"))
      (node (ref "C3") (pin "1") (pinfunction "1_1") (pintype "passive"))
      (node (ref "C4") (pin "1") (pinfunction "1_1") (pintype "passive"))
      (node (ref "Q1") (pin "4") (pinfunction "S_4") (pintype "passive"))
      (node (ref "Q3") (pin "C") (pinfunction "C_C") (pintype "passive"))
      (node (ref "R1") (pin "2") (pinfunction "2_2") (pintype "passive"))
      (node (ref "R13") (pin "2") (pinfunction "2_2") (pintype "passive"))
      (node (ref "R2") (pin "2") (pinfunction "2_2") (pintype "passive"))
      (node (ref "X1") (pin "1") (pinfunction "KL_1") (pintype "passive"))
    )
    (net (code "45") (name "Net-(Q2-G)") (class "Default")
      (node (ref "Q2") (pin "3") (pinfunction "G_3") (pintype "passive"))
      (node (ref "Q5") (pin "C") (pinfunction "C_C") (pintype "passive"))
      (node (ref "R5") (pin "1") (pinfunction "1_1") (pintype "passive"))
    )
    (net (code "46") (name "Net-(Q5-PadB)") (class "Default")
      (node (ref "Q5") (pin "B") (pinfunction "B_B") (pintype "passive"))
      (node (ref "R9") (pin "2") (pinfunction "2_2") (pintype "passive"))
    )
    (net (code "47") (name "Net-(Q7-B)") (class "Default")
      (node (ref "C23") (pin "1") (pinfunction "1_1") (pintype "passive"))
      (node (ref "Q7") (pin "1") (pinfunction "B_1") (pintype "passive"))
      (node (ref "R31") (pin "1") (pinfunction "1_1") (pintype "passive"))
      (node (ref "R35") (pin "2") (pinfunction "2_2") (pintype "passive"))
    )
    (net (code "48") (name "Net-(Q8-B)") (class "Default")
      (node (ref "C26") (pin "1") (pinfunction "1_1") (pintype "passive"))
      (node (ref "Q8") (pin "1") (pinfunction "B_1") (pintype "passive"))
      (node (ref "R42") (pin "1") (pinfunction "1_1") (pintype "passive"))
      (node (ref "R46") (pin "2") (pinfunction "2_2") (pintype "passive"))
    )
    (net (code "49") (name "Net-(R1-Pad1)") (class "Default")
      (node (ref "R1") (pin "1") (pinfunction "1_1") (pintype "passive"))
      (node (ref "R6") (pin "1") (pinfunction "1_1") (pintype "passive"))
      (node (ref "R7") (pin "2") (pinfunction "2_2") (pintype "passive"))
    )
    (net (code "50") (name "Net-(X1B-KL)") (class "Default")
      (node (ref "R167") (pin "1") (pinfunction "1_1") (pintype "passive"))
      (node (ref "R17") (pin "2") (pinfunction "2_2") (pintype "passive"))
      (node (ref "X1") (pin "2") (pinfunction "KL_2") (pintype "passive"))
    )
    (net (code "51") (name "RTS") (class "Default")
      (node (ref "IC6") (pin "4") (pinfunction "C_4") (pintype "bidirectional"))
      (node (ref "J6") (pin "3") (pinfunction "P_3") (pintype "bidirectional"))
      (node (ref "R25") (pin "1") (pinfunction "1_1") (pintype "passive"))
    )
    (net (code "52") (name "RX") (class "Default")
      (node (ref "J6") (pin "4") (pinfunction "P_4") (pintype "bidirectional"))
      (node (ref "R24") (pin "2") (pinfunction "2_2") (pintype "passive"))
    )
    (net (code "53") (name "SWDCLK_2") (class "Default")
      (node (ref "IC7") (pin "37") (pinfunction "PA14_37") (pintype "bidirectional"))
      (node (ref "JP1") (pin "4") (pinfunction "4_4") (pintype "passive"))
    )
    (net (code "54") (name "SWDDAT_2") (class "Default")
      (node (ref "IC7") (pin "34") (pinfunction "PA13_34") (pintype "bidirectional"))
      (node (ref "JP1") (pin "2") (pinfunction "2_2") (pintype "passive"))
    )
    (net (code "55") (name "TIM1_CH1") (class "Default")
      (node (ref "IC7") (pin "29") (pinfunction "PA8_29") (pintype "bidirectional"))
      (node (ref "R13") (pin "1") (pinfunction "1_1") (pintype "passive"))
      (node (ref "R15") (pin "1") (pinfunction "1_1") (pintype "passive"))
    )
    (net (code "56") (name "TX") (class "Default")
      (node (ref "IC4") (pin "4") (pinfunction "C_4") (pintype "bidirectional"))
      (node (ref "J6") (pin "5") (pinfunction "P_5") (pintype "bidirectional"))
      (node (ref "R20") (pin "1") (pinfunction "1_1") (pintype "passive"))
    )
    (net (code "57") (name "USART1_CTS") (class "Default")
      (node (ref "IC7") (pin "32") (pinfunction "PA11_32") (pintype "bidirectional"))
      (node (ref "IC8") (pin "4") (pinfunction "C_4") (pintype "bidirectional"))
      (node (ref "R27") (pin "2") (pinfunction "2_2") (pintype "passive"))
    )
    (net (code "58") (name "USART1_RTS") (class "Default")
      (node (ref "IC7") (pin "33") (pinfunction "PA12_33") (pintype "bidirectional"))
      (node (ref "R26") (pin "1") (pinfunction "1_1") (pintype "passive"))
    )
    (net (code "59") (name "USART1_RX") (class "Default")
      (node (ref "IC5") (pin "4") (pinfunction "C_4") (pintype "bidirectional"))
      (node (ref "IC7") (pin "31") (pinfunction "PA10_31") (pintype "bidirectional"))
      (node (ref "R23") (pin "2") (pinfunction "2_2") (pintype "passive"))
    )
    (net (code "60") (name "USART1_TX") (class "Default")
      (node (ref "IC7") (pin "30") (pinfunction "PA9_30") (pintype "bidirectional"))
      (node (ref "R21") (pin "1") (pinfunction "1_1") (pintype "passive"))
    )
    (net (code "61") (name "VBAT") (class "Default")
      (node (ref "Q2") (pin "4") (pinfunction "S_4") (pintype "passive"))
      (node (ref "Q7") (pin "3") (pinfunction "E_3") (pintype "passive"))
      (node (ref "R31") (pin "2") (pinfunction "2_2") (pintype "passive"))
      (node (ref "R34") (pin "2") (pinfunction "2_2") (pintype "passive"))
      (node (ref "R5") (pin "2") (pinfunction "2_2") (pintype "passive"))
      (node (ref "X2") (pin "1") (pinfunction "KL_1") (pintype "passive"))
    )
    (net (code "62") (name "VCC_EXT") (class "Default")
      (node (ref "J6") (pin "8") (pinfunction "P_8") (pintype "bidirectional"))
      (node (ref "R20") (pin "2") (pinfunction "2_2") (pintype "passive"))
      (node (ref "R25") (pin "2") (pinfunction "2_2") (pintype "passive"))
    )
    (net (code "63") (name "VMPPT") (class "Default")
      (node (ref "C10") (pin "1") (pinfunction "1_1") (pintype "passive"))
      (node (ref "C15") (pin "1") (pinfunction "1_1") (pintype "passive"))
      (node (ref "C17") (pin "1") (pinfunction "1_1") (pintype "passive"))
      (node (ref "C18") (pin "1") (pinfunction "1_1") (pintype "passive"))
      (node (ref "C19") (pin "1") (pinfunction "1_1") (pintype "passive"))
      (node (ref "C20") (pin "1") (pinfunction "1_1") (pintype "passive"))
      (node (ref "C21") (pin "1") (pinfunction "1_1") (pintype "passive"))
      (node (ref "C29") (pin "1") (pinfunction "1_1") (pintype "passive"))
      (node (ref "IC11") (pin "7") (pinfunction "VCC_7") (pintype "power_in"))
      (node (ref "IC2") (pin "7") (pinfunction "VCC_7") (pintype "power_in"))
      (node (ref "IC3") (pin "2") (pinfunction "OUT_2") (pintype "passive"))
      (node (ref "IC7") (pin "1") (pinfunction "VBAT_1") (pintype "bidirectional"))
      (node (ref "IC7") (pin "24") (pinfunction "VDD_24") (pintype "bidirectional"))
      (node (ref "IC7") (pin "36") (pinfunction "VDD_36") (pintype "bidirectional"))
      (node (ref "IC7") (pin "48") (pinfunction "VDD_48") (pintype "bidirectional"))
      (node (ref "L2") (pin "1") (pinfunction "1_1") (pintype "passive"))
      (node (ref "R22") (pin "2") (pinfunction "2_2") (pintype "passive"))
      (node (ref "R23") (pin "1") (pinfunction "1_1") (pintype "passive"))
      (node (ref "R27") (pin "1") (pinfunction "1_1") (pintype "passive"))
      (node (ref "R29") (pin "1") (pinfunction "1_1") (pintype "passive"))
      (node (ref "R32") (pin "2") (pinfunction "2_2") (pintype "passive"))
      (node (ref "R41") (pin "2") (pinfunction "2_2") (pintype "passive"))
      (node (ref "R44") (pin "2") (pinfunction "2_2") (pintype "passive"))
      (node (ref "R48") (pin "2") (pinfunction "2_2") (pintype "passive"))
      (node (ref "R55") (pin "2") (pinfunction "2_2") (pintype "passive"))
    )
    (net (code "64") (name "unconnected-(IC7-OSC_IN-Pad5)") (class "Default")
      (node (ref "IC7") (pin "5") (pinfunction "OSC_IN_5") (pintype "bidirectional"))
    )
    (net (code "65") (name "unconnected-(IC7-OSC_OUT-Pad6)") (class "Default")
      (node (ref "IC7") (pin "6") (pinfunction "OSC_OUT_6") (pintype "bidirectional"))
    )
    (net (code "66") (name "unconnected-(IC7-PA15-Pad38)") (class "Default")
      (node (ref "IC7") (pin "38") (pinfunction "PA15_38") (pintype "bidirectional"))
    )
    (net (code "67") (name "unconnected-(IC7-PB0-Pad18)") (class "Default")
      (node (ref "IC7") (pin "18") (pinfunction "PB0_18") (pintype "bidirectional"))
    )
    (net (code "68") (name "unconnected-(IC7-PB1-Pad19)") (class "Default")
      (node (ref "IC7") (pin "19") (pinfunction "PB1_19") (pintype "bidirectional"))
    )
    (net (code "69") (name "unconnected-(IC7-PB2-Pad20)") (class "Default")
      (node (ref "IC7") (pin "20") (pinfunction "PB2_20") (pintype "bidirectional"))
    )
    (net (code "70") (name "unconnected-(IC7-PB3-Pad39)") (class "Default")
      (node (ref "IC7") (pin "39") (pinfunction "PB3_39") (pintype "bidirectional"))
    )
    (net (code "71") (name "unconnected-(IC7-PB4-Pad40)") (class "Default")
      (node (ref "IC7") (pin "40") (pinfunction "PB4_40") (pintype "bidirectional"))
    )
    (net (code "72") (name "unconnected-(IC7-PB5-Pad41)") (class "Default")
      (node (ref "IC7") (pin "41") (pinfunction "PB5_41") (pintype "bidirectional"))
    )
    (net (code "73") (name "unconnected-(IC7-PB6-Pad42)") (class "Default")
      (node (ref "IC7") (pin "42") (pinfunction "PB6_42") (pintype "bidirectional"))
    )
    (net (code "74") (name "unconnected-(IC7-PB7-Pad43)") (class "Default")
      (node (ref "IC7") (pin "43") (pinfunction "PB7_43") (pintype "bidirectional"))
    )
    (net (code "75") (name "unconnected-(IC7-PB8-Pad45)") (class "Default")
      (node (ref "IC7") (pin "45") (pinfunction "PB8_45") (pintype "bidirectional"))
    )
    (net (code "76") (name "unconnected-(IC7-PB9-Pad46)") (class "Default")
      (node (ref "IC7") (pin "46") (pinfunction "PB9_46") (pintype "bidirectional"))
    )
    (net (code "77") (name "unconnected-(IC7-PB10-Pad21)") (class "Default")
      (node (ref "IC7") (pin "21") (pinfunction "PB10_21") (pintype "bidirectional"))
    )
    (net (code "78") (name "unconnected-(IC7-PB11-Pad22)") (class "Default")
      (node (ref "IC7") (pin "22") (pinfunction "PB11_22") (pintype "bidirectional"))
    )
    (net (code "79") (name "unconnected-(IC7-PB12-Pad25)") (class "Default")
      (node (ref "IC7") (pin "25") (pinfunction "PB12_25") (pintype "bidirectional"))
    )
    (net (code "80") (name "unconnected-(IC7-PB13-Pad26)") (class "Default")
      (node (ref "IC7") (pin "26") (pinfunction "PB13_26") (pintype "bidirectional"))
    )
    (net (code "81") (name "unconnected-(IC7-PB14-Pad27)") (class "Default")
      (node (ref "IC7") (pin "27") (pinfunction "PB14_27") (pintype "bidirectional"))
    )
    (net (code "82") (name "unconnected-(IC7-PC13-TAMPER-RTC-Pad2)") (class "Default")
      (node (ref "IC7") (pin "2") (pinfunction "PC13-TAMPER-RTC_2") (pintype "bidirectional"))
    )
    (net (code "83") (name "unconnected-(IC7-PC14-OSC32_IN-Pad3)") (class "Default")
      (node (ref "IC7") (pin "3") (pinfunction "PC14-OSC32_IN_3") (pintype "bidirectional"))
    )
    (net (code "84") (name "unconnected-(IC7-PC15-OSC32_OUT-Pad4)") (class "Default")
      (node (ref "IC7") (pin "4") (pinfunction "PC15-OSC32_OUT_4") (pintype "bidirectional"))
    )
    (net (code "85") (name "unconnected-(J6F-P-Pad6)") (class "Default")
      (node (ref "J6") (pin "6") (pinfunction "P_6") (pintype "bidirectional"))
    )
    (net (code "86") (name "unconnected-(J6G-P-Pad7)") (class "Default")
      (node (ref "J6") (pin "7") (pinfunction "P_7") (pintype "bidirectional"))
    )
  )
)
